# zumy_carrier_board.net
KiCad netlist of a schematic drawn in EAGLE
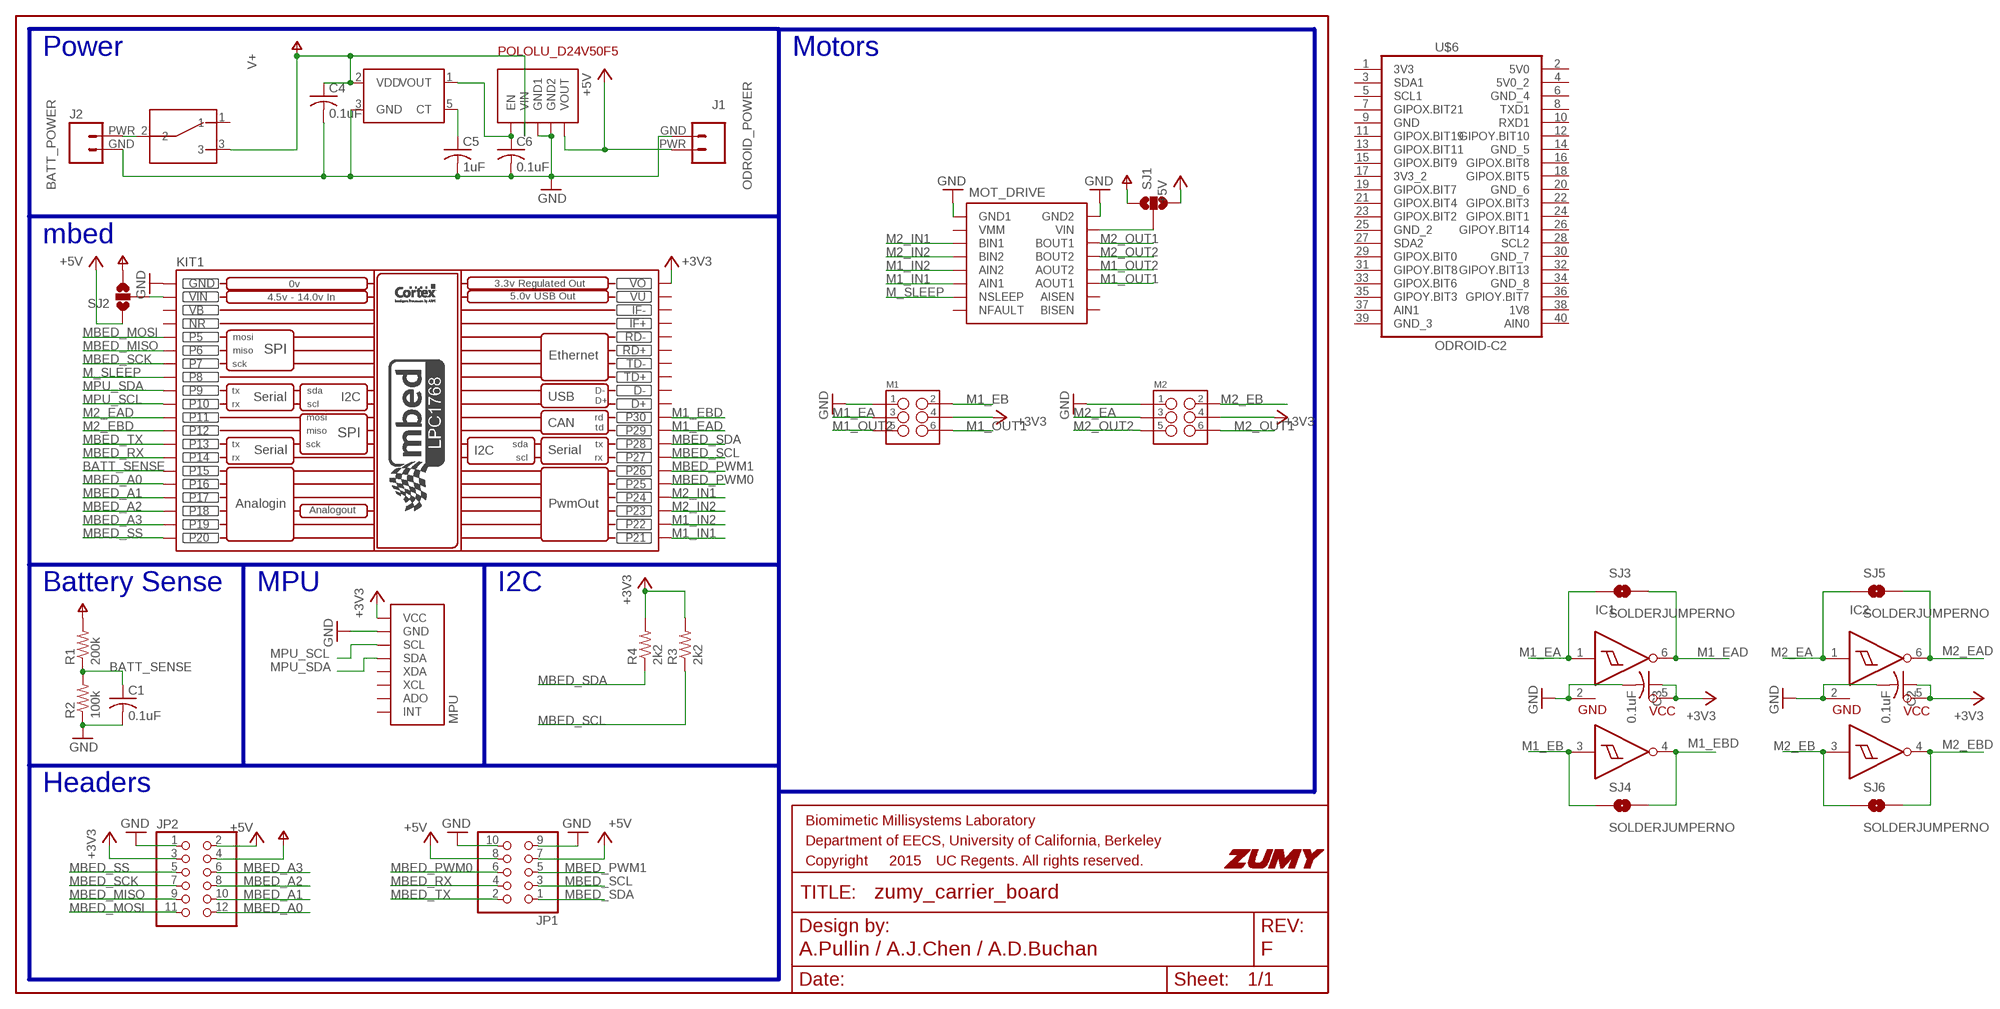
[diagram p0: schematic, sheet 1]

(export (version "E")
  (design (tool "Eeschema 10.0.6"))
  (components
    (comp (ref "C1")
      (value "0.1uF")
      (footprint "eagle-import:C1206")
      (libsource (lib "eagle-import") (part "C-USC1206"))
    )
    (comp (ref "C2")
      (value "0.1uF")
      (footprint "eagle-import:C1206")
      (libsource (lib "eagle-import") (part "C-USC1206"))
    )
    (comp (ref "C3")
      (value "0.1uF")
      (footprint "eagle-import:C1206")
      (libsource (lib "eagle-import") (part "C-USC1206"))
    )
    (comp (ref "C4")
      (value "0.1uF")
      (footprint "eagle-import:C1206")
      (libsource (lib "eagle-import") (part "C-USC1206"))
    )
    (comp (ref "C5")
      (value "1uF")
      (footprint "eagle-import:C1206")
      (libsource (lib "eagle-import") (part "C-USC1206"))
    )
    (comp (ref "C6")
      (value "0.1uF")
      (footprint "eagle-import:C1206")
      (libsource (lib "eagle-import") (part "C-USC1206"))
    )
    (comp (ref "IC1")
      (value "SN74AUP2G17")
      (footprint "eagle-import:SC-70-6")
      (libsource (lib "eagle-import") (part "SN74AUP2G17"))
    )
    (comp (ref "IC2")
      (value "SN74AUP2G17")
      (footprint "eagle-import:SC-70-6")
      (libsource (lib "eagle-import") (part "SN74AUP2G17"))
    )
    (comp (ref "J1")
      (value "ODROID_POWER")
      (footprint "eagle-import:ODOIRD_PWR")
      (libsource (lib "eagle-import") (part "ODROID_POWER"))
    )
    (comp (ref "J2")
      (value "BATT_POWER")
      (footprint "eagle-import:BATT_POWER")
      (libsource (lib "eagle-import") (part "BATT_POWER"))
    )
    (comp (ref "JP1")
      (value "PINHD-2X5")
      (footprint "eagle-import:2X05")
      (libsource (lib "eagle-import") (part "PINHD-2X5"))
    )
    (comp (ref "JP2")
      (value "PINHD-2X6")
      (footprint "eagle-import:2X06")
      (libsource (lib "eagle-import") (part "PINHD-2X6"))
    )
    (comp (ref "KIT1")
      (value "MBED_NXP_LPC1768")
      (footprint "eagle-import:MBED-KIT")
      (libsource (lib "eagle-import") (part "MBED_NXP_LPC1768"))
    )
    (comp (ref "M1")
      (value "M03X2SHROUD")
      (footprint "eagle-import:2X3-SHROUDED")
      (libsource (lib "eagle-import") (part "M03X2SHROUD"))
    )
    (comp (ref "M2")
      (value "M03X2SHROUD")
      (footprint "eagle-import:2X3-SHROUDED")
      (libsource (lib "eagle-import") (part "M03X2SHROUD"))
    )
    (comp (ref "MOT_DRIVE")
      (value "POLOLU_DRV8833_MODULE")
      (footprint "eagle-import:POLOLU_DRV8833_MODULE")
      (libsource (lib "eagle-import") (part "POLOLU_DRV8833_MODULE"))
    )
    (comp (ref "MPU")
      (value "ITG/MPU_MODULE")
      (footprint "eagle-import:ITG_MPU_MODULE")
      (libsource (lib "eagle-import") (part "ITG/MPU_MODULE"))
    )
    (comp (ref "R1")
      (value "200k")
      (footprint "eagle-import:R1206")
      (libsource (lib "eagle-import") (part "R-US_R1206"))
    )
    (comp (ref "R2")
      (value "100k")
      (footprint "eagle-import:R1206")
      (libsource (lib "eagle-import") (part "R-US_R1206"))
    )
    (comp (ref "R3")
      (value "2k2")
      (footprint "eagle-import:R1206")
      (libsource (lib "eagle-import") (part "R-US_R1206"))
    )
    (comp (ref "R4")
      (value "2k2")
      (footprint "eagle-import:R1206")
      (libsource (lib "eagle-import") (part "R-US_R1206"))
    )
    (comp (ref "SJ1")
      (value "SOLDERJUMPER_2WAYT")
      (footprint "eagle-import:SJ_2")
      (libsource (lib "eagle-import") (part "SOLDERJUMPER_2WAYT"))
    )
    (comp (ref "SJ2")
      (value "SOLDERJUMPER_2WAYT")
      (footprint "eagle-import:SJ_2")
      (libsource (lib "eagle-import") (part "SOLDERJUMPER_2WAYT"))
    )
    (comp (ref "SJ3")
      (value "SOLDERJUMPERNO")
      (footprint "eagle-import:SJ_2S-NO")
      (libsource (lib "eagle-import") (part "SOLDERJUMPERNO"))
    )
    (comp (ref "SJ4")
      (value "SOLDERJUMPERNO")
      (footprint "eagle-import:SJ_2S-NO")
      (libsource (lib "eagle-import") (part "SOLDERJUMPERNO"))
    )
    (comp (ref "SJ5")
      (value "SOLDERJUMPERNO")
      (footprint "eagle-import:SJ_2S-NO")
      (libsource (lib "eagle-import") (part "SOLDERJUMPERNO"))
    )
    (comp (ref "SJ6")
      (value "SOLDERJUMPERNO")
      (footprint "eagle-import:SJ_2S-NO")
      (libsource (lib "eagle-import") (part "SOLDERJUMPERNO"))
    )
    (comp (ref "SW1")
      (value "500SSP1S1M6QEA")
      (footprint "eagle-import:500SSP1S1M6QEA_SWITCH")
      (libsource (lib "eagle-import") (part "500SSP1S1M6QEA"))
    )
    (comp (ref "U$2")
      (value "BD5260G")
      (footprint "eagle-import:SOT23-5")
      (libsource (lib "eagle-import") (part "BD5260G"))
    )
    (comp (ref "U$3")
      (value "ZUMY_LOGO")
      (footprint "eagle-import:ZUMY_LOGO_SILK")
      (libsource (lib "eagle-import") (part "ZUMY_LOGO"))
    )
    (comp (ref "U$5")
      (value "POLOLU_D24V50F5")
      (footprint "eagle-import:POLOLU_D24V50F5")
      (libsource (lib "eagle-import") (part "POLOLU_D24V50F5"))
    )
    (comp (ref "U$6")
      (value "ODROID-C2")
      (footprint "eagle-import:ODROID-C2-BOARD")
      (libsource (lib "eagle-import") (part "ODROID-C2"))
    )
  )
  (nets
    (net (code "1") (name "+3V3") (class "Default")
      (node (ref "C2") (pin "1") (pinfunction "1_1") (pintype "passive"))
      (node (ref "C3") (pin "1") (pinfunction "1_1") (pintype "passive"))
      (node (ref "IC1") (pin "5") (pinfunction "VCC_5") (pintype "output"))
      (node (ref "IC2") (pin "5") (pinfunction "VCC_5") (pintype "output"))
      (node (ref "JP2") (pin "3") (pinfunction "3_3") (pintype "passive"))
      (node (ref "KIT1") (pin "VOUT") (pinfunction "VO_VOUT") (pintype "power_in"))
      (node (ref "M1") (pin "4") (pinfunction "4_4") (pintype "bidirectional"))
      (node (ref "M2") (pin "4") (pinfunction "4_4") (pintype "bidirectional"))
      (node (ref "MPU") (pin "VCC") (pinfunction "VCC_VCC") (pintype "bidirectional"))
      (node (ref "R3") (pin "2") (pinfunction "2_2") (pintype "passive"))
      (node (ref "R4") (pin "2") (pinfunction "2_2") (pintype "passive"))
    )
    (net (code "2") (name "+5V") (class "Default")
      (node (ref "J1") (pin "PWR") (pinfunction "PWR_PWR") (pintype "passive"))
      (node (ref "JP1") (pin "7") (pinfunction "7_7") (pintype "passive"))
      (node (ref "JP1") (pin "8") (pinfunction "8_8") (pintype "passive"))
      (node (ref "JP2") (pin "2") (pinfunction "2_2") (pintype "passive"))
      (node (ref "SJ1") (pin "3") (pinfunction "3_3") (pintype "passive"))
      (node (ref "SJ2") (pin "1") (pinfunction "1_1") (pintype "passive"))
      (node (ref "U$5") (pin "VOUT") (pinfunction "VOUT_VOUT") (pintype "bidirectional"))
    )
    (net (code "3") (name "/BATT_SENSE") (class "Default")
      (node (ref "C1") (pin "1") (pinfunction "1_1") (pintype "passive"))
      (node (ref "KIT1") (pin "P$15") (pinfunction "P15_P$15") (pintype "bidirectional"))
      (node (ref "R1") (pin "1") (pinfunction "1_1") (pintype "passive"))
      (node (ref "R2") (pin "2") (pinfunction "2_2") (pintype "passive"))
    )
    (net (code "4") (name "/M1_EA") (class "Default")
      (node (ref "IC1") (pin "1") (pinfunction "1A_1") (pintype "input"))
      (node (ref "M1") (pin "3") (pinfunction "3_3") (pintype "bidirectional"))
      (node (ref "SJ3") (pin "1") (pinfunction "1_1") (pintype "passive"))
    )
    (net (code "5") (name "/M1_EAD") (class "Default")
      (node (ref "IC1") (pin "6") (pinfunction "1Y_6") (pintype "output"))
      (node (ref "KIT1") (pin "P$29") (pinfunction "P29_P$29") (pintype "bidirectional"))
      (node (ref "SJ3") (pin "2") (pinfunction "2_2") (pintype "passive"))
    )
    (net (code "6") (name "/M1_EB") (class "Default")
      (node (ref "IC1") (pin "3") (pinfunction "2A_3") (pintype "input"))
      (node (ref "M1") (pin "2") (pinfunction "2_2") (pintype "bidirectional"))
      (node (ref "SJ4") (pin "1") (pinfunction "1_1") (pintype "passive"))
    )
    (net (code "7") (name "/M1_EBD") (class "Default")
      (node (ref "IC1") (pin "4") (pinfunction "2Y_4") (pintype "output"))
      (node (ref "KIT1") (pin "P$30") (pinfunction "P30_P$30") (pintype "bidirectional"))
      (node (ref "SJ4") (pin "2") (pinfunction "2_2") (pintype "passive"))
    )
    (net (code "8") (name "/M1_IN1") (class "Default")
      (node (ref "KIT1") (pin "P$21") (pinfunction "P21_P$21") (pintype "bidirectional"))
      (node (ref "MOT_DRIVE") (pin "AIN1") (pinfunction "AIN1_AIN1") (pintype "bidirectional"))
    )
    (net (code "9") (name "/M1_IN2") (class "Default")
      (node (ref "KIT1") (pin "P$22") (pinfunction "P22_P$22") (pintype "bidirectional"))
      (node (ref "MOT_DRIVE") (pin "AIN2") (pinfunction "AIN2_AIN2") (pintype "bidirectional"))
    )
    (net (code "10") (name "/M1_OUT1") (class "Default")
      (node (ref "M1") (pin "6") (pinfunction "6_6") (pintype "bidirectional"))
      (node (ref "MOT_DRIVE") (pin "AOUT1") (pinfunction "AOUT1_AOUT1") (pintype "bidirectional"))
    )
    (net (code "11") (name "/M1_OUT2") (class "Default")
      (node (ref "M1") (pin "5") (pinfunction "5_5") (pintype "bidirectional"))
      (node (ref "MOT_DRIVE") (pin "AOUT2") (pinfunction "AOUT2_AOUT2") (pintype "bidirectional"))
    )
    (net (code "12") (name "/M2_EA") (class "Default")
      (node (ref "IC2") (pin "1") (pinfunction "1A_1") (pintype "input"))
      (node (ref "M2") (pin "3") (pinfunction "3_3") (pintype "bidirectional"))
      (node (ref "SJ5") (pin "1") (pinfunction "1_1") (pintype "passive"))
    )
    (net (code "13") (name "/M2_EAD") (class "Default")
      (node (ref "IC2") (pin "6") (pinfunction "1Y_6") (pintype "output"))
      (node (ref "KIT1") (pin "P$11") (pinfunction "P11_P$11") (pintype "bidirectional"))
      (node (ref "SJ5") (pin "2") (pinfunction "2_2") (pintype "passive"))
    )
    (net (code "14") (name "/M2_EB") (class "Default")
      (node (ref "IC2") (pin "3") (pinfunction "2A_3") (pintype "input"))
      (node (ref "M2") (pin "2") (pinfunction "2_2") (pintype "bidirectional"))
      (node (ref "SJ6") (pin "1") (pinfunction "1_1") (pintype "passive"))
    )
    (net (code "15") (name "/M2_EBD") (class "Default")
      (node (ref "IC2") (pin "4") (pinfunction "2Y_4") (pintype "output"))
      (node (ref "KIT1") (pin "P$12") (pinfunction "P12_P$12") (pintype "bidirectional"))
      (node (ref "SJ6") (pin "2") (pinfunction "2_2") (pintype "passive"))
    )
    (net (code "16") (name "/M2_IN1") (class "Default")
      (node (ref "KIT1") (pin "P$24") (pinfunction "P24_P$24") (pintype "bidirectional"))
      (node (ref "MOT_DRIVE") (pin "BIN1") (pinfunction "BIN1_BIN1") (pintype "bidirectional"))
    )
    (net (code "17") (name "/M2_IN2") (class "Default")
      (node (ref "KIT1") (pin "P$23") (pinfunction "P23_P$23") (pintype "bidirectional"))
      (node (ref "MOT_DRIVE") (pin "BIN2") (pinfunction "BIN2_BIN2") (pintype "bidirectional"))
    )
    (net (code "18") (name "/M2_OUT1") (class "Default")
      (node (ref "M2") (pin "6") (pinfunction "6_6") (pintype "bidirectional"))
      (node (ref "MOT_DRIVE") (pin "BOUT1") (pinfunction "BOUT1_BOUT1") (pintype "bidirectional"))
    )
    (net (code "19") (name "/M2_OUT2") (class "Default")
      (node (ref "M2") (pin "5") (pinfunction "5_5") (pintype "bidirectional"))
      (node (ref "MOT_DRIVE") (pin "BOUT2") (pinfunction "BOUT2_BOUT2") (pintype "bidirectional"))
    )
    (net (code "20") (name "/MBED_A0") (class "Default")
      (node (ref "JP2") (pin "12") (pinfunction "12_12") (pintype "passive"))
      (node (ref "KIT1") (pin "P$16") (pinfunction "P16_P$16") (pintype "bidirectional"))
    )
    (net (code "21") (name "/MBED_A1") (class "Default")
      (node (ref "JP2") (pin "10") (pinfunction "10_10") (pintype "passive"))
      (node (ref "KIT1") (pin "P$17") (pinfunction "P17_P$17") (pintype "bidirectional"))
    )
    (net (code "22") (name "/MBED_A2") (class "Default")
      (node (ref "JP2") (pin "8") (pinfunction "8_8") (pintype "passive"))
      (node (ref "KIT1") (pin "P$18") (pinfunction "P18_P$18") (pintype "bidirectional"))
    )
    (net (code "23") (name "/MBED_A3") (class "Default")
      (node (ref "JP2") (pin "6") (pinfunction "6_6") (pintype "passive"))
      (node (ref "KIT1") (pin "P$19") (pinfunction "P19_P$19") (pintype "bidirectional"))
    )
    (net (code "24") (name "/MBED_MISO") (class "Default")
      (node (ref "JP2") (pin "9") (pinfunction "9_9") (pintype "passive"))
      (node (ref "KIT1") (pin "P$6") (pinfunction "P6_P$6") (pintype "bidirectional"))
    )
    (net (code "25") (name "/MBED_MOSI") (class "Default")
      (node (ref "JP2") (pin "11") (pinfunction "11_11") (pintype "passive"))
      (node (ref "KIT1") (pin "P$5") (pinfunction "P5_P$5") (pintype "bidirectional"))
    )
    (net (code "26") (name "/MBED_PWM0") (class "Default")
      (node (ref "JP1") (pin "6") (pinfunction "6_6") (pintype "passive"))
      (node (ref "KIT1") (pin "P$25") (pinfunction "P25_P$25") (pintype "bidirectional"))
    )
    (net (code "27") (name "/MBED_PWM1") (class "Default")
      (node (ref "JP1") (pin "5") (pinfunction "5_5") (pintype "passive"))
      (node (ref "KIT1") (pin "P$26") (pinfunction "P26_P$26") (pintype "bidirectional"))
    )
    (net (code "28") (name "/MBED_RX") (class "Default")
      (node (ref "JP1") (pin "4") (pinfunction "4_4") (pintype "passive"))
      (node (ref "KIT1") (pin "P$14") (pinfunction "P14_P$14") (pintype "bidirectional"))
    )
    (net (code "29") (name "/MBED_SCK") (class "Default")
      (node (ref "JP2") (pin "7") (pinfunction "7_7") (pintype "passive"))
      (node (ref "KIT1") (pin "P$7") (pinfunction "P7_P$7") (pintype "bidirectional"))
    )
    (net (code "30") (name "/MBED_SCL") (class "Default")
      (node (ref "JP1") (pin "3") (pinfunction "3_3") (pintype "passive"))
      (node (ref "KIT1") (pin "P$27") (pinfunction "P27_P$27") (pintype "bidirectional"))
      (node (ref "R3") (pin "1") (pinfunction "1_1") (pintype "passive"))
    )
    (net (code "31") (name "/MBED_SDA") (class "Default")
      (node (ref "JP1") (pin "1") (pinfunction "1_1") (pintype "passive"))
      (node (ref "KIT1") (pin "P$28") (pinfunction "P28_P$28") (pintype "bidirectional"))
      (node (ref "R4") (pin "1") (pinfunction "1_1") (pintype "passive"))
    )
    (net (code "32") (name "/MBED_SS") (class "Default")
      (node (ref "JP2") (pin "5") (pinfunction "5_5") (pintype "passive"))
      (node (ref "KIT1") (pin "P$20") (pinfunction "P20_P$20") (pintype "bidirectional"))
    )
    (net (code "33") (name "/MBED_TX") (class "Default")
      (node (ref "JP1") (pin "2") (pinfunction "2_2") (pintype "passive"))
      (node (ref "KIT1") (pin "P$13") (pinfunction "P13_P$13") (pintype "bidirectional"))
    )
    (net (code "34") (name "/MPU_SCL") (class "Default")
      (node (ref "KIT1") (pin "P$10") (pinfunction "P10_P$10") (pintype "bidirectional"))
      (node (ref "MPU") (pin "SCL") (pinfunction "SCL_SCL") (pintype "bidirectional"))
    )
    (net (code "35") (name "/MPU_SDA") (class "Default")
      (node (ref "KIT1") (pin "P$9") (pinfunction "P9_P$9") (pintype "bidirectional"))
      (node (ref "MPU") (pin "SDA") (pinfunction "SDA_SDA") (pintype "bidirectional"))
    )
    (net (code "36") (name "/M_SLEEP") (class "Default")
      (node (ref "KIT1") (pin "P$8") (pinfunction "P8_P$8") (pintype "bidirectional"))
      (node (ref "MOT_DRIVE") (pin "NSLEEP") (pinfunction "NSLEEP_NSLEEP") (pintype "bidirectional"))
    )
    (net (code "37") (name "/NR") (class "Default")
      (node (ref "KIT1") (pin "NR") (pinfunction "NR_NR") (pintype "power_in"))
    )
    (net (code "38") (name "/VB") (class "Default")
      (node (ref "KIT1") (pin "VB") (pinfunction "VB_VB") (pintype "power_in"))
    )
    (net (code "39") (name "/VU") (class "Default")
      (node (ref "KIT1") (pin "VU") (pinfunction "VU_VU") (pintype "power_in"))
    )
    (net (code "40") (name "GND") (class "Default")
      (node (ref "C1") (pin "2") (pinfunction "2_2") (pintype "passive"))
      (node (ref "C2") (pin "2") (pinfunction "2_2") (pintype "passive"))
      (node (ref "C3") (pin "2") (pinfunction "2_2") (pintype "passive"))
      (node (ref "C4") (pin "2") (pinfunction "2_2") (pintype "passive"))
      (node (ref "C5") (pin "2") (pinfunction "2_2") (pintype "passive"))
      (node (ref "C6") (pin "2") (pinfunction "2_2") (pintype "passive"))
      (node (ref "IC1") (pin "2") (pinfunction "GND_2") (pintype "input"))
      (node (ref "IC2") (pin "2") (pinfunction "GND_2") (pintype "input"))
      (node (ref "J1") (pin "GND") (pinfunction "GND_GND") (pintype "passive"))
      (node (ref "J2") (pin "GND") (pinfunction "GND_GND") (pintype "passive"))
      (node (ref "JP1") (pin "10") (pinfunction "10_10") (pintype "passive"))
      (node (ref "JP1") (pin "9") (pinfunction "9_9") (pintype "passive"))
      (node (ref "JP2") (pin "1") (pinfunction "1_1") (pintype "passive"))
      (node (ref "KIT1") (pin "GND") (pinfunction "GND_GND") (pintype "power_in"))
      (node (ref "M1") (pin "1") (pinfunction "1_1") (pintype "bidirectional"))
      (node (ref "M2") (pin "1") (pinfunction "1_1") (pintype "bidirectional"))
      (node (ref "MOT_DRIVE") (pin "GND1") (pinfunction "GND1_GND1") (pintype "bidirectional"))
      (node (ref "MOT_DRIVE") (pin "GND2") (pinfunction "GND2_GND2") (pintype "bidirectional"))
      (node (ref "MPU") (pin "GND") (pinfunction "GND_GND") (pintype "bidirectional"))
      (node (ref "R2") (pin "1") (pinfunction "1_1") (pintype "passive"))
      (node (ref "U$2") (pin "3") (pinfunction "GND_3") (pintype "bidirectional"))
      (node (ref "U$5") (pin "GND1") (pinfunction "GND1_GND1") (pintype "bidirectional"))
      (node (ref "U$5") (pin "GND2") (pinfunction "GND2_GND2") (pintype "bidirectional"))
    )
    (net (code "41") (name "Net-(J2-PadPWR)") (class "Default")
      (node (ref "J2") (pin "PWR") (pinfunction "PWR_PWR") (pintype "passive"))
      (node (ref "SW1") (pin "2") (pinfunction "2_2") (pintype "bidirectional"))
    )
    (net (code "42") (name "Net-(KIT1-PadVIN)") (class "Default")
      (node (ref "KIT1") (pin "VIN") (pinfunction "VIN_VIN") (pintype "power_in"))
      (node (ref "SJ2") (pin "2") (pinfunction "2_2") (pintype "passive"))
    )
    (net (code "43") (name "Net-(MOT_DRIVE-PadVIN)") (class "Default")
      (node (ref "MOT_DRIVE") (pin "VIN") (pinfunction "VIN_VIN") (pintype "bidirectional"))
      (node (ref "SJ1") (pin "2") (pinfunction "2_2") (pintype "passive"))
    )
    (net (code "44") (name "Net-(U$2-CT)") (class "Default")
      (node (ref "C5") (pin "1") (pinfunction "1_1") (pintype "passive"))
      (node (ref "U$2") (pin "5") (pinfunction "CT_5") (pintype "bidirectional"))
    )
    (net (code "45") (name "Net-(U$2-VOUT)") (class "Default")
      (node (ref "C6") (pin "1") (pinfunction "1_1") (pintype "passive"))
      (node (ref "U$2") (pin "1") (pinfunction "VOUT_1") (pintype "bidirectional"))
      (node (ref "U$5") (pin "EN") (pinfunction "EN_EN") (pintype "bidirectional"))
    )
    (net (code "46") (name "V+") (class "Default")
      (node (ref "C4") (pin "1") (pinfunction "1_1") (pintype "passive"))
      (node (ref "JP2") (pin "4") (pinfunction "4_4") (pintype "passive"))
      (node (ref "R1") (pin "2") (pinfunction "2_2") (pintype "passive"))
      (node (ref "SJ1") (pin "1") (pinfunction "1_1") (pintype "passive"))
      (node (ref "SJ2") (pin "3") (pinfunction "3_3") (pintype "passive"))
      (node (ref "SW1") (pin "3") (pinfunction "3_3") (pintype "bidirectional"))
      (node (ref "U$2") (pin "2") (pinfunction "VDD_2") (pintype "bidirectional"))
      (node (ref "U$5") (pin "VIN") (pinfunction "VIN_VIN") (pintype "bidirectional"))
    )
    (net (code "47") (name "unconnected-(KIT1-PadD+)") (class "Default")
      (node (ref "KIT1") (pin "D+") (pinfunction "D+_D+") (pintype "bidirectional"))
    )
    (net (code "48") (name "unconnected-(KIT1-PadD-)") (class "Default")
      (node (ref "KIT1") (pin "D-") (pinfunction "D-_D-") (pintype "bidirectional"))
    )
    (net (code "49") (name "unconnected-(KIT1-PadIF+)") (class "Default")
      (node (ref "KIT1") (pin "IF+") (pinfunction "IF+_IF+") (pintype "bidirectional"))
    )
    (net (code "50") (name "unconnected-(KIT1-PadIF-)") (class "Default")
      (node (ref "KIT1") (pin "IF-") (pinfunction "IF-_IF-") (pintype "bidirectional"))
    )
    (net (code "51") (name "unconnected-(KIT1-PadRD+)") (class "Default")
      (node (ref "KIT1") (pin "RD+") (pinfunction "RD+_RD+") (pintype "bidirectional"))
    )
    (net (code "52") (name "unconnected-(KIT1-PadRD-)") (class "Default")
      (node (ref "KIT1") (pin "RD-") (pinfunction "RD-_RD-") (pintype "bidirectional"))
    )
    (net (code "53") (name "unconnected-(KIT1-PadTD+)") (class "Default")
      (node (ref "KIT1") (pin "TD+") (pinfunction "TD+_TD+") (pintype "bidirectional"))
    )
    (net (code "54") (name "unconnected-(KIT1-PadTD-)") (class "Default")
      (node (ref "KIT1") (pin "TD-") (pinfunction "TD-_TD-") (pintype "bidirectional"))
    )
    (net (code "55") (name "unconnected-(MOT_DRIVE-PadAISEN)") (class "Default")
      (node (ref "MOT_DRIVE") (pin "AISEN") (pinfunction "AISEN_AISEN") (pintype "bidirectional"))
    )
    (net (code "56") (name "unconnected-(MOT_DRIVE-PadBISEN)") (class "Default")
      (node (ref "MOT_DRIVE") (pin "BISEN") (pinfunction "BISEN_BISEN") (pintype "bidirectional"))
    )
    (net (code "57") (name "unconnected-(MOT_DRIVE-PadNFAULT)") (class "Default")
      (node (ref "MOT_DRIVE") (pin "NFAULT") (pinfunction "NFAULT_NFAULT") (pintype "bidirectional"))
    )
    (net (code "58") (name "unconnected-(MOT_DRIVE-PadVMM)") (class "Default")
      (node (ref "MOT_DRIVE") (pin "VMM") (pinfunction "VMM_VMM") (pintype "bidirectional"))
    )
    (net (code "59") (name "unconnected-(MPU-PadADO)") (class "Default")
      (node (ref "MPU") (pin "ADO") (pinfunction "ADO_ADO") (pintype "bidirectional"))
    )
    (net (code "60") (name "unconnected-(MPU-PadINT)") (class "Default")
      (node (ref "MPU") (pin "INT") (pinfunction "INT_INT") (pintype "bidirectional"))
    )
    (net (code "61") (name "unconnected-(MPU-PadXCL)") (class "Default")
      (node (ref "MPU") (pin "XCL") (pinfunction "XCL_XCL") (pintype "bidirectional"))
    )
    (net (code "62") (name "unconnected-(MPU-PadXDA)") (class "Default")
      (node (ref "MPU") (pin "XDA") (pinfunction "XDA_XDA") (pintype "bidirectional"))
    )
    (net (code "63") (name "unconnected-(SW1-Pad1)") (class "Default")
      (node (ref "SW1") (pin "1") (pinfunction "1_1") (pintype "bidirectional"))
    )
    (net (code "64") (name "unconnected-(U$6-1V8-Pad38)") (class "Default")
      (node (ref "U$6") (pin "38") (pinfunction "1V8_38") (pintype "passive"))
    )
    (net (code "65") (name "unconnected-(U$6-3V3-Pad1)") (class "Default")
      (node (ref "U$6") (pin "1") (pinfunction "3V3_1") (pintype "passive"))
    )
    (net (code "66") (name "unconnected-(U$6-3V3_2-Pad17)") (class "Default")
      (node (ref "U$6") (pin "17") (pinfunction "3V3_2_17") (pintype "passive"))
    )
    (net (code "67") (name "unconnected-(U$6-5V0-Pad2)") (class "Default")
      (node (ref "U$6") (pin "2") (pinfunction "5V0_2") (pintype "passive"))
    )
    (net (code "68") (name "unconnected-(U$6-5V0_2-Pad4)") (class "Default")
      (node (ref "U$6") (pin "4") (pinfunction "5V0_2_4") (pintype "passive"))
    )
    (net (code "69") (name "unconnected-(U$6-AIN0-Pad40)") (class "Default")
      (node (ref "U$6") (pin "40") (pinfunction "AIN0_40") (pintype "passive"))
    )
    (net (code "70") (name "unconnected-(U$6-AIN1-Pad37)") (class "Default")
      (node (ref "U$6") (pin "37") (pinfunction "AIN1_37") (pintype "passive"))
    )
    (net (code "71") (name "unconnected-(U$6-GIPOX.BIT0-Pad29)") (class "Default")
      (node (ref "U$6") (pin "29") (pinfunction "GIPOX.BIT0_29") (pintype "passive"))
    )
    (net (code "72") (name "unconnected-(U$6-GIPOX.BIT1-Pad24)") (class "Default")
      (node (ref "U$6") (pin "24") (pinfunction "GIPOX.BIT1_24") (pintype "passive"))
    )
    (net (code "73") (name "unconnected-(U$6-GIPOX.BIT2-Pad23)") (class "Default")
      (node (ref "U$6") (pin "23") (pinfunction "GIPOX.BIT2_23") (pintype "passive"))
    )
    (net (code "74") (name "unconnected-(U$6-GIPOX.BIT3-Pad22)") (class "Default")
      (node (ref "U$6") (pin "22") (pinfunction "GIPOX.BIT3_22") (pintype "passive"))
    )
    (net (code "75") (name "unconnected-(U$6-GIPOX.BIT4-Pad21)") (class "Default")
      (node (ref "U$6") (pin "21") (pinfunction "GIPOX.BIT4_21") (pintype "passive"))
    )
    (net (code "76") (name "unconnected-(U$6-GIPOX.BIT5-Pad18)") (class "Default")
      (node (ref "U$6") (pin "18") (pinfunction "GIPOX.BIT5_18") (pintype "passive"))
    )
    (net (code "77") (name "unconnected-(U$6-GIPOX.BIT6-Pad33)") (class "Default")
      (node (ref "U$6") (pin "33") (pinfunction "GIPOX.BIT6_33") (pintype "passive"))
    )
    (net (code "78") (name "unconnected-(U$6-GIPOX.BIT7-Pad19)") (class "Default")
      (node (ref "U$6") (pin "19") (pinfunction "GIPOX.BIT7_19") (pintype "passive"))
    )
    (net (code "79") (name "unconnected-(U$6-GIPOX.BIT8-Pad16)") (class "Default")
      (node (ref "U$6") (pin "16") (pinfunction "GIPOX.BIT8_16") (pintype "passive"))
    )
    (net (code "80") (name "unconnected-(U$6-GIPOX.BIT9-Pad15)") (class "Default")
      (node (ref "U$6") (pin "15") (pinfunction "GIPOX.BIT9_15") (pintype "passive"))
    )
    (net (code "81") (name "unconnected-(U$6-GIPOX.BIT11-Pad13)") (class "Default")
      (node (ref "U$6") (pin "13") (pinfunction "GIPOX.BIT11_13") (pintype "passive"))
    )
    (net (code "82") (name "unconnected-(U$6-GIPOX.BIT19-Pad11)") (class "Default")
      (node (ref "U$6") (pin "11") (pinfunction "GIPOX.BIT19_11") (pintype "passive"))
    )
    (net (code "83") (name "unconnected-(U$6-GIPOX.BIT21-Pad7)") (class "Default")
      (node (ref "U$6") (pin "7") (pinfunction "GIPOX.BIT21_7") (pintype "passive"))
    )
    (net (code "84") (name "unconnected-(U$6-GIPOY.BIT3-Pad35)") (class "Default")
      (node (ref "U$6") (pin "35") (pinfunction "GIPOY.BIT3_35") (pintype "passive"))
    )
    (net (code "85") (name "unconnected-(U$6-GIPOY.BIT8-Pad31)") (class "Default")
      (node (ref "U$6") (pin "31") (pinfunction "GIPOY.BIT8_31") (pintype "passive"))
    )
    (net (code "86") (name "unconnected-(U$6-GIPOY.BIT10-Pad12)") (class "Default")
      (node (ref "U$6") (pin "12") (pinfunction "GIPOY.BIT10_12") (pintype "passive"))
    )
    (net (code "87") (name "unconnected-(U$6-GIPOY.BIT13-Pad32)") (class "Default")
      (node (ref "U$6") (pin "32") (pinfunction "GIPOY.BIT13_32") (pintype "passive"))
    )
    (net (code "88") (name "unconnected-(U$6-GIPOY.BIT14-Pad26)") (class "Default")
      (node (ref "U$6") (pin "26") (pinfunction "GIPOY.BIT14_26") (pintype "passive"))
    )
    (net (code "89") (name "unconnected-(U$6-GND-Pad9)") (class "Default")
      (node (ref "U$6") (pin "9") (pinfunction "GND_9") (pintype "passive"))
    )
    (net (code "90") (name "unconnected-(U$6-GND_2-Pad25)") (class "Default")
      (node (ref "U$6") (pin "25") (pinfunction "GND_2_25") (pintype "passive"))
    )
    (net (code "91") (name "unconnected-(U$6-GND_3-Pad39)") (class "Default")
      (node (ref "U$6") (pin "39") (pinfunction "GND_3_39") (pintype "passive"))
    )
    (net (code "92") (name "unconnected-(U$6-GND_4-Pad6)") (class "Default")
      (node (ref "U$6") (pin "6") (pinfunction "GND_4_6") (pintype "passive"))
    )
    (net (code "93") (name "unconnected-(U$6-GND_5-Pad14)") (class "Default")
      (node (ref "U$6") (pin "14") (pinfunction "GND_5_14") (pintype "passive"))
    )
    (net (code "94") (name "unconnected-(U$6-GND_6-Pad20)") (class "Default")
      (node (ref "U$6") (pin "20") (pinfunction "GND_6_20") (pintype "passive"))
    )
    (net (code "95") (name "unconnected-(U$6-GND_7-Pad30)") (class "Default")
      (node (ref "U$6") (pin "30") (pinfunction "GND_7_30") (pintype "passive"))
    )
    (net (code "96") (name "unconnected-(U$6-GND_8-Pad34)") (class "Default")
      (node (ref "U$6") (pin "34") (pinfunction "GND_8_34") (pintype "passive"))
    )
    (net (code "97") (name "unconnected-(U$6-GPIOY.BIT7-Pad36)") (class "Default")
      (node (ref "U$6") (pin "36") (pinfunction "GPIOY.BIT7_36") (pintype "passive"))
    )
    (net (code "98") (name "unconnected-(U$6-RXD1-Pad10)") (class "Default")
      (node (ref "U$6") (pin "10") (pinfunction "RXD1_10") (pintype "passive"))
    )
    (net (code "99") (name "unconnected-(U$6-SCL1-Pad5)") (class "Default")
      (node (ref "U$6") (pin "5") (pinfunction "SCL1_5") (pintype "passive"))
    )
    (net (code "100") (name "unconnected-(U$6-SCL2-Pad28)") (class "Default")
      (node (ref "U$6") (pin "28") (pinfunction "SCL2_28") (pintype "passive"))
    )
    (net (code "101") (name "unconnected-(U$6-SDA1-Pad3)") (class "Default")
      (node (ref "U$6") (pin "3") (pinfunction "SDA1_3") (pintype "passive"))
    )
    (net (code "102") (name "unconnected-(U$6-SDA2-Pad27)") (class "Default")
      (node (ref "U$6") (pin "27") (pinfunction "SDA2_27") (pintype "passive"))
    )
    (net (code "103") (name "unconnected-(U$6-TXD1-Pad8)") (class "Default")
      (node (ref "U$6") (pin "8") (pinfunction "TXD1_8") (pintype "passive"))
    )
  )
)
